# test-jauge.net
KiCad netlist of a schematic drawn in EAGLE
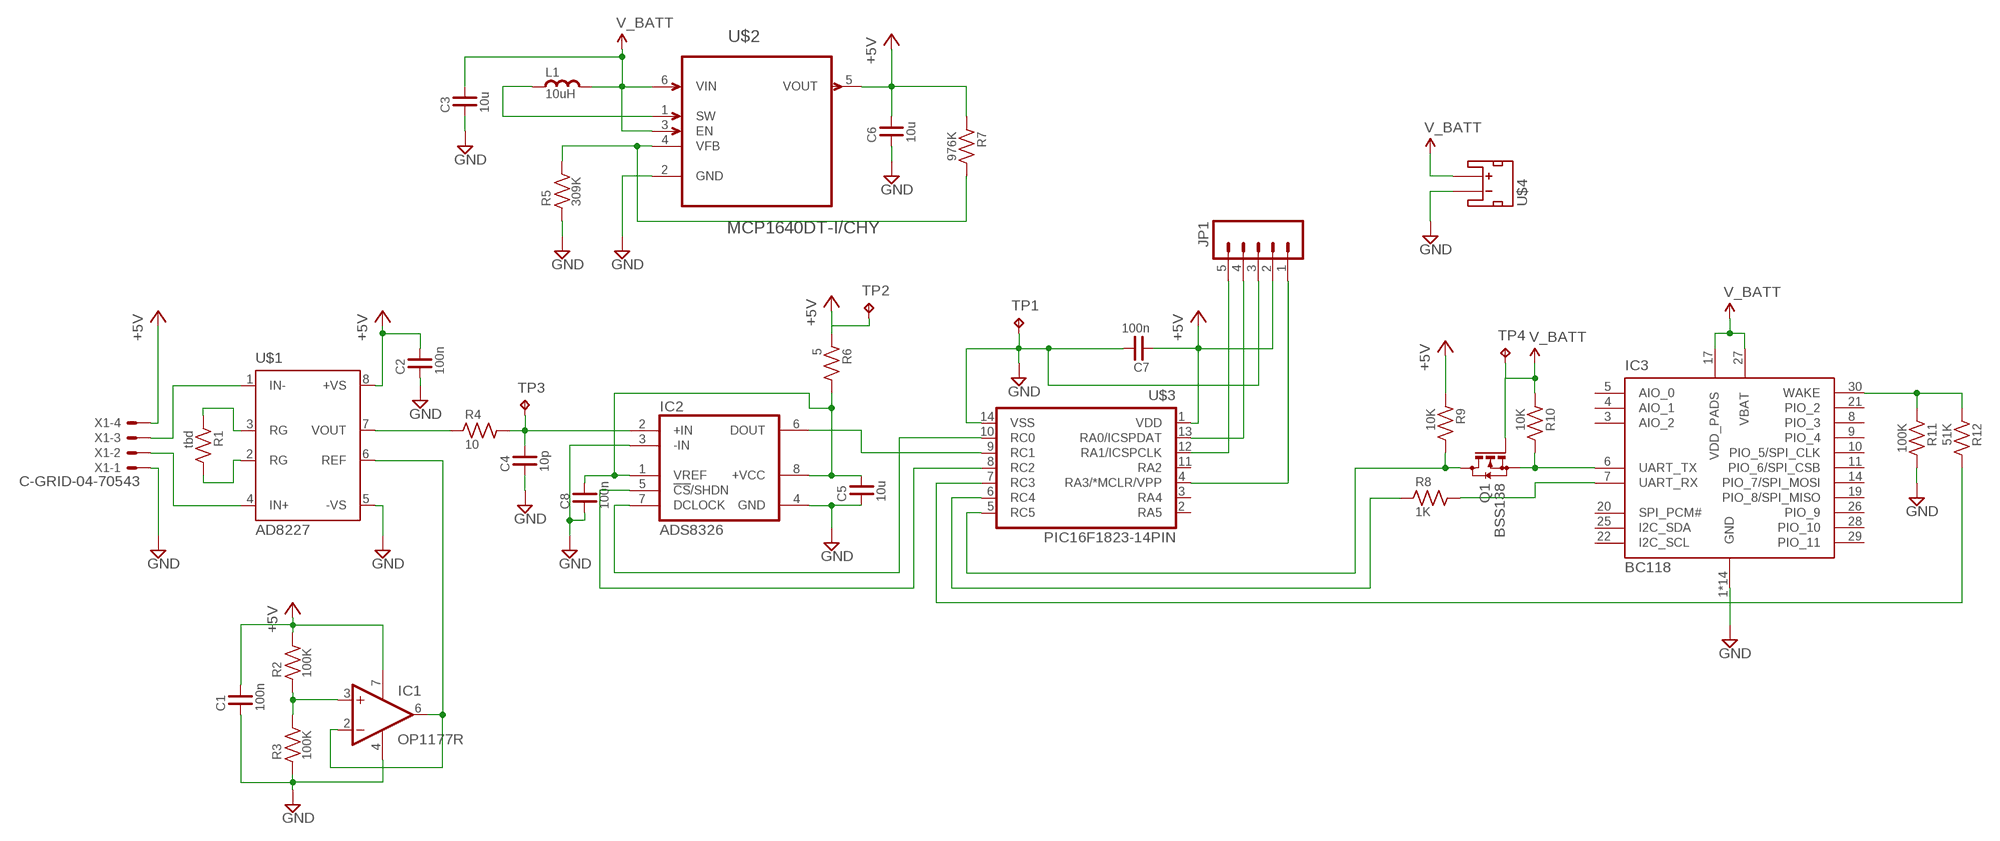
[diagram p0: schematic, sheet 1]

(export (version "E")
  (design (tool "Eeschema 10.0.6"))
  (components
    (comp (ref "C1")
      (value "100n")
      (footprint "eagle-import:C1206")
      (libsource (lib "eagle-import") (part "C1206"))
    )
    (comp (ref "C2")
      (value "100n")
      (footprint "eagle-import:C1206")
      (libsource (lib "eagle-import") (part "C1206"))
    )
    (comp (ref "C3")
      (value "10u")
      (footprint "eagle-import:C1206")
      (libsource (lib "eagle-import") (part "C1206"))
    )
    (comp (ref "C4")
      (value "10p")
      (footprint "eagle-import:C1206")
      (libsource (lib "eagle-import") (part "C1206"))
    )
    (comp (ref "C5")
      (value "10u")
      (footprint "eagle-import:C1206")
      (libsource (lib "eagle-import") (part "C1206"))
    )
    (comp (ref "C6")
      (value "10u")
      (footprint "eagle-import:C1206")
      (libsource (lib "eagle-import") (part "C1206"))
    )
    (comp (ref "C7")
      (value "100n")
      (footprint "eagle-import:C1206")
      (libsource (lib "eagle-import") (part "C1206"))
    )
    (comp (ref "C8")
      (value "100n")
      (footprint "eagle-import:C1206")
      (libsource (lib "eagle-import") (part "C1206"))
    )
    (comp (ref "IC1")
      (value "OP1177R")
      (footprint "eagle-import:SOIC8")
      (libsource (lib "eagle-import") (part "OP1177R"))
    )
    (comp (ref "IC2")
      (value "ADS8326")
      (footprint "eagle-import:MSOP08")
      (fields (field (name "MF") "TEXAS INSTRUMENT CONNECTORS") (field (name "MPN") "ADS7816EC/250"))
      (libsource (lib "eagle-import") (part "ADS7816E"))
    )
    (comp (ref "IC3")
      (value "BC118")
      (footprint "eagle-import:BC118")
      (libsource (lib "eagle-import") (part "BC118"))
    )
    (comp (ref "JP1")
      (value "M05PTH")
      (footprint "eagle-import:1X05")
      (libsource (lib "eagle-import") (part "M05PTH"))
    )
    (comp (ref "L1")
      (value "10uH")
      (footprint "eagle-import:L1206")
      (libsource (lib "eagle-import") (part "LU1206"))
    )
    (comp (ref "Q1")
      (value "BSS138")
      (footprint "eagle-import:SOT23")
      (libsource (lib "eagle-import") (part "BSS123"))
    )
    (comp (ref "R1")
      (value "tbd")
      (footprint "eagle-import:R1206")
      (libsource (lib "eagle-import") (part "RU1206"))
    )
    (comp (ref "R2")
      (value "100K")
      (footprint "eagle-import:R1206")
      (libsource (lib "eagle-import") (part "RU1206"))
    )
    (comp (ref "R3")
      (value "100K")
      (footprint "eagle-import:R1206")
      (libsource (lib "eagle-import") (part "RU1206"))
    )
    (comp (ref "R4")
      (value "10")
      (footprint "eagle-import:R1206")
      (libsource (lib "eagle-import") (part "RU1206"))
    )
    (comp (ref "R5")
      (value "309K")
      (footprint "eagle-import:R1206")
      (libsource (lib "eagle-import") (part "RU1206"))
    )
    (comp (ref "R6")
      (value "5")
      (footprint "eagle-import:R1206")
      (libsource (lib "eagle-import") (part "RU1206"))
    )
    (comp (ref "R7")
      (value "976K")
      (footprint "eagle-import:R1206")
      (libsource (lib "eagle-import") (part "RU1206"))
    )
    (comp (ref "R8")
      (value "1K")
      (footprint "eagle-import:R1206")
      (libsource (lib "eagle-import") (part "RU1206"))
    )
    (comp (ref "R9")
      (value "10K")
      (footprint "eagle-import:R1206")
      (libsource (lib "eagle-import") (part "RU1206"))
    )
    (comp (ref "R10")
      (value "10K")
      (footprint "eagle-import:R1206")
      (libsource (lib "eagle-import") (part "RU1206"))
    )
    (comp (ref "R11")
      (value "100K")
      (footprint "eagle-import:R1206")
      (libsource (lib "eagle-import") (part "RU1206"))
    )
    (comp (ref "R12")
      (value "51K")
      (footprint "eagle-import:R1206")
      (libsource (lib "eagle-import") (part "RU1206"))
    )
    (comp (ref "TP1")
      (value "TPTP08R")
      (footprint "eagle-import:TP08R")
      (libsource (lib "eagle-import") (part "TPTP08R"))
    )
    (comp (ref "TP2")
      (value "TPTP08R")
      (footprint "eagle-import:TP08R")
      (libsource (lib "eagle-import") (part "TPTP08R"))
    )
    (comp (ref "TP3")
      (value "TPTP08R")
      (footprint "eagle-import:TP08R")
      (libsource (lib "eagle-import") (part "TPTP08R"))
    )
    (comp (ref "TP4")
      (value "TPTP08R")
      (footprint "eagle-import:TP08R")
      (libsource (lib "eagle-import") (part "TPTP08R"))
    )
    (comp (ref "U$1")
      (value "AD8227")
      (footprint "eagle-import:SO8")
      (libsource (lib "eagle-import") (part "AD822X"))
    )
    (comp (ref "U$2")
      (value "MCP1640DT-I/CHY")
      (footprint "eagle-import:SOT95P270X145-6N")
      (libsource (lib "eagle-import") (part "MCP1640DT-I/CHY"))
    )
    (comp (ref "U$3")
      (value "PIC16F1823-14PIN")
      (footprint "eagle-import:SOIC-14")
      (libsource (lib "eagle-import") (part "PIC16F1823-14PIN"))
    )
    (comp (ref "U$4")
      (value "JST-2-PTH")
      (footprint "eagle-import:JST-2-PTH")
      (libsource (lib "eagle-import") (part "JST-2-PTH"))
    )
    (comp (ref "X1")
      (value "C-GRID-04-70543")
      (footprint "eagle-import:70543-04")
      (libsource (lib "eagle-import") (part "C-GRID-04-70543"))
    )
  )
  (nets
    (net (code "1") (name "+5V") (class "Default")
      (node (ref "C1") (pin "2") (pinfunction "2_2") (pintype "passive"))
      (node (ref "C2") (pin "2") (pinfunction "2_2") (pintype "passive"))
      (node (ref "C6") (pin "2") (pinfunction "2_2") (pintype "passive"))
      (node (ref "C7") (pin "1") (pinfunction "1_1") (pintype "passive"))
      (node (ref "IC1") (pin "7") (pinfunction "V+_7") (pintype "power_in"))
      (node (ref "JP1") (pin "2") (pinfunction "2_2") (pintype "passive"))
      (node (ref "R2") (pin "2") (pinfunction "2_2") (pintype "passive"))
      (node (ref "R6") (pin "1") (pinfunction "1_1") (pintype "passive"))
      (node (ref "R7") (pin "1") (pinfunction "1_1") (pintype "passive"))
      (node (ref "R9") (pin "1") (pinfunction "1_1") (pintype "passive"))
      (node (ref "TP2") (pin "TP") (pinfunction "TP_TP") (pintype "input"))
      (node (ref "U$1") (pin "8") (pinfunction "+VS_8") (pintype "power_in"))
      (node (ref "U$2") (pin "5") (pinfunction "VOUT_5") (pintype "output"))
      (node (ref "U$3") (pin "1") (pinfunction "VDD_1") (pintype "power_in"))
      (node (ref "X1") (pin "4") (pinfunction "S_4") (pintype "passive"))
    )
    (net (code "2") (name "GND") (class "Default")
      (node (ref "C1") (pin "1") (pinfunction "1_1") (pintype "passive"))
      (node (ref "C2") (pin "1") (pinfunction "1_1") (pintype "passive"))
      (node (ref "C3") (pin "1") (pinfunction "1_1") (pintype "passive"))
      (node (ref "C4") (pin "1") (pinfunction "1_1") (pintype "passive"))
      (node (ref "C5") (pin "1") (pinfunction "1_1") (pintype "passive"))
      (node (ref "C6") (pin "1") (pinfunction "1_1") (pintype "passive"))
      (node (ref "C7") (pin "2") (pinfunction "2_2") (pintype "passive"))
      (node (ref "C8") (pin "1") (pinfunction "1_1") (pintype "passive"))
      (node (ref "IC1") (pin "4") (pinfunction "V-_4") (pintype "power_in"))
      (node (ref "IC2") (pin "3") (pinfunction "-IN_3") (pintype "input"))
      (node (ref "IC2") (pin "4") (pinfunction "GND_4") (pintype "power_in"))
      (node (ref "IC3") (pin "1") (pinfunction "GND_1") (pintype "power_in"))
      (node (ref "IC3") (pin "12") (pinfunction "GND_12") (pintype "power_in"))
      (node (ref "IC3") (pin "13") (pinfunction "GND_13") (pintype "power_in"))
      (node (ref "IC3") (pin "15") (pinfunction "GND_15") (pintype "power_in"))
      (node (ref "IC3") (pin "16") (pinfunction "GND_16") (pintype "power_in"))
      (node (ref "IC3") (pin "18") (pinfunction "GND_18") (pintype "power_in"))
      (node (ref "IC3") (pin "2") (pinfunction "GND_2") (pintype "power_in"))
      (node (ref "IC3") (pin "23") (pinfunction "GND_23") (pintype "power_in"))
      (node (ref "IC3") (pin "24") (pinfunction "GND_24") (pintype "power_in"))
      (node (ref "IC3") (pin "31") (pinfunction "GND_31") (pintype "power_in"))
      (node (ref "IC3") (pin "32") (pinfunction "GND_32") (pintype "power_in"))
      (node (ref "IC3") (pin "33") (pinfunction "GND_33") (pintype "power_in"))
      (node (ref "IC3") (pin "34") (pinfunction "GND_34") (pintype "power_in"))
      (node (ref "IC3") (pin "35") (pinfunction "GND_35") (pintype "power_in"))
      (node (ref "JP1") (pin "3") (pinfunction "3_3") (pintype "passive"))
      (node (ref "R11") (pin "2") (pinfunction "2_2") (pintype "passive"))
      (node (ref "R3") (pin "1") (pinfunction "1_1") (pintype "passive"))
      (node (ref "R5") (pin "1") (pinfunction "1_1") (pintype "passive"))
      (node (ref "TP1") (pin "TP") (pinfunction "TP_TP") (pintype "input"))
      (node (ref "U$1") (pin "5") (pinfunction "-VS_5") (pintype "power_in"))
      (node (ref "U$2") (pin "2") (pinfunction "GND_2") (pintype "passive"))
      (node (ref "U$3") (pin "14") (pinfunction "VSS_14") (pintype "power_in"))
      (node (ref "U$4") (pin "-") (pinfunction "-_-") (pintype "bidirectional"))
      (node (ref "X1") (pin "1") (pinfunction "S_1") (pintype "passive"))
    )
    (net (code "3") (name "Net-(IC1-+IN)") (class "Default")
      (node (ref "IC1") (pin "3") (pinfunction "+IN_3") (pintype "input"))
      (node (ref "R2") (pin "1") (pinfunction "1_1") (pintype "passive"))
      (node (ref "R3") (pin "2") (pinfunction "2_2") (pintype "passive"))
    )
    (net (code "4") (name "Net-(IC1--IN)") (class "Default")
      (node (ref "IC1") (pin "2") (pinfunction "-IN_2") (pintype "input"))
      (node (ref "IC1") (pin "6") (pinfunction "OUT_6") (pintype "output"))
      (node (ref "U$1") (pin "6") (pinfunction "REF_6") (pintype "input"))
    )
    (net (code "5") (name "Net-(IC2-+IN)") (class "Default")
      (node (ref "C4") (pin "2") (pinfunction "2_2") (pintype "passive"))
      (node (ref "IC2") (pin "2") (pinfunction "+IN_2") (pintype "input"))
      (node (ref "R4") (pin "2") (pinfunction "2_2") (pintype "passive"))
      (node (ref "TP3") (pin "TP") (pinfunction "TP_TP") (pintype "input"))
    )
    (net (code "6") (name "Net-(IC2-+VCC)") (class "Default")
      (node (ref "C5") (pin "2") (pinfunction "2_2") (pintype "passive"))
      (node (ref "C8") (pin "2") (pinfunction "2_2") (pintype "passive"))
      (node (ref "IC2") (pin "1") (pinfunction "VREF_1") (pintype "input"))
      (node (ref "IC2") (pin "8") (pinfunction "+VCC_8") (pintype "power_in"))
      (node (ref "R6") (pin "2") (pinfunction "2_2") (pintype "passive"))
    )
    (net (code "7") (name "Net-(IC2-DCLOCK)") (class "Default")
      (node (ref "IC2") (pin "7") (pinfunction "DCLOCK_7") (pintype "input"))
      (node (ref "U$3") (pin "10") (pinfunction "RC0_10") (pintype "bidirectional"))
    )
    (net (code "8") (name "Net-(IC2-DOUT)") (class "Default")
      (node (ref "IC2") (pin "6") (pinfunction "DOUT_6") (pintype "output"))
      (node (ref "U$3") (pin "9") (pinfunction "RC1_9") (pintype "bidirectional"))
    )
    (net (code "9") (name "Net-(IC2-~{CS}{slash}SHDN)") (class "Default")
      (node (ref "IC2") (pin "5") (pinfunction "~{CS}/SHDN_5") (pintype "input"))
      (node (ref "U$3") (pin "8") (pinfunction "RC2_8") (pintype "bidirectional"))
    )
    (net (code "10") (name "Net-(IC3-UART_RX)") (class "Default")
      (node (ref "IC3") (pin "7") (pinfunction "UART_RX_7") (pintype "bidirectional"))
      (node (ref "R8") (pin "2") (pinfunction "2_2") (pintype "passive"))
    )
    (net (code "11") (name "Net-(IC3-UART_TX)") (class "Default")
      (node (ref "IC3") (pin "6") (pinfunction "UART_TX_6") (pintype "bidirectional"))
      (node (ref "Q1") (pin "2") (pinfunction "S_2") (pintype "passive"))
      (node (ref "R10") (pin "2") (pinfunction "2_2") (pintype "passive"))
    )
    (net (code "12") (name "Net-(IC3-WAKE)") (class "Default")
      (node (ref "IC3") (pin "30") (pinfunction "WAKE_30") (pintype "bidirectional"))
      (node (ref "R11") (pin "1") (pinfunction "1_1") (pintype "passive"))
      (node (ref "R12") (pin "1") (pinfunction "1_1") (pintype "passive"))
    )
    (net (code "13") (name "Net-(Q1-D)") (class "Default")
      (node (ref "Q1") (pin "3") (pinfunction "D_3") (pintype "passive"))
      (node (ref "R9") (pin "2") (pinfunction "2_2") (pintype "passive"))
      (node (ref "U$3") (pin "5") (pinfunction "RC5_5") (pintype "bidirectional"))
    )
    (net (code "14") (name "Net-(R1-Pad1)") (class "Default")
      (node (ref "R1") (pin "1") (pinfunction "1_1") (pintype "passive"))
      (node (ref "U$1") (pin "3") (pinfunction "RG_3") (pintype "input"))
    )
    (net (code "15") (name "Net-(R1-Pad2)") (class "Default")
      (node (ref "R1") (pin "2") (pinfunction "2_2") (pintype "passive"))
      (node (ref "U$1") (pin "2") (pinfunction "RG_2") (pintype "input"))
    )
    (net (code "16") (name "Net-(U$1-IN+)") (class "Default")
      (node (ref "U$1") (pin "4") (pinfunction "IN+_4") (pintype "input"))
      (node (ref "X1") (pin "2") (pinfunction "S_2") (pintype "passive"))
    )
    (net (code "17") (name "Net-(U$1-IN-)") (class "Default")
      (node (ref "U$1") (pin "1") (pinfunction "IN-_1") (pintype "input"))
      (node (ref "X1") (pin "3") (pinfunction "S_3") (pintype "passive"))
    )
    (net (code "18") (name "Net-(U$1-VOUT)") (class "Default")
      (node (ref "R4") (pin "1") (pinfunction "1_1") (pintype "passive"))
      (node (ref "U$1") (pin "7") (pinfunction "VOUT_7") (pintype "output"))
    )
    (net (code "19") (name "Net-(U$2-SW)") (class "Default")
      (node (ref "L1") (pin "1") (pinfunction "1_1") (pintype "passive"))
      (node (ref "U$2") (pin "1") (pinfunction "SW_1") (pintype "input"))
    )
    (net (code "20") (name "Net-(U$2-VFB)") (class "Default")
      (node (ref "R5") (pin "2") (pinfunction "2_2") (pintype "passive"))
      (node (ref "R7") (pin "2") (pinfunction "2_2") (pintype "passive"))
      (node (ref "U$2") (pin "4") (pinfunction "VFB_4") (pintype "input"))
    )
    (net (code "21") (name "Net-(U$3-RA0{slash}ICSPDAT)") (class "Default")
      (node (ref "JP1") (pin "4") (pinfunction "4_4") (pintype "passive"))
      (node (ref "U$3") (pin "13") (pinfunction "RA0/ICSPDAT_13") (pintype "bidirectional"))
    )
    (net (code "22") (name "Net-(U$3-RA1{slash}ICSPCLK)") (class "Default")
      (node (ref "JP1") (pin "5") (pinfunction "5_5") (pintype "passive"))
      (node (ref "U$3") (pin "12") (pinfunction "RA1/ICSPCLK_12") (pintype "bidirectional"))
    )
    (net (code "23") (name "Net-(U$3-RA3{slash}*MCLR{slash}VPP)") (class "Default")
      (node (ref "JP1") (pin "1") (pinfunction "1_1") (pintype "passive"))
      (node (ref "U$3") (pin "4") (pinfunction "RA3/*MCLR/VPP_4") (pintype "input"))
    )
    (net (code "24") (name "Net-(U$3-RC3)") (class "Default")
      (node (ref "R12") (pin "2") (pinfunction "2_2") (pintype "passive"))
      (node (ref "U$3") (pin "7") (pinfunction "RC3_7") (pintype "bidirectional"))
    )
    (net (code "25") (name "Net-(U$3-RC4)") (class "Default")
      (node (ref "R8") (pin "1") (pinfunction "1_1") (pintype "passive"))
      (node (ref "U$3") (pin "6") (pinfunction "RC4_6") (pintype "bidirectional"))
    )
    (net (code "26") (name "V_BATT") (class "Default")
      (node (ref "C3") (pin "2") (pinfunction "2_2") (pintype "passive"))
      (node (ref "IC3") (pin "17") (pinfunction "VDD_PADS_17") (pintype "power_in"))
      (node (ref "IC3") (pin "27") (pinfunction "VBAT_27") (pintype "bidirectional"))
      (node (ref "L1") (pin "2") (pinfunction "2_2") (pintype "passive"))
      (node (ref "Q1") (pin "1") (pinfunction "G_1") (pintype "passive"))
      (node (ref "R10") (pin "1") (pinfunction "1_1") (pintype "passive"))
      (node (ref "TP4") (pin "TP") (pinfunction "TP_TP") (pintype "input"))
      (node (ref "U$2") (pin "3") (pinfunction "EN_3") (pintype "input"))
      (node (ref "U$2") (pin "6") (pinfunction "VIN_6") (pintype "input"))
      (node (ref "U$4") (pin "+") (pinfunction "+_+") (pintype "bidirectional"))
    )
    (net (code "27") (name "unconnected-(IC3-AIO_0-Pad5)") (class "Default")
      (node (ref "IC3") (pin "5") (pinfunction "AIO_0_5") (pintype "bidirectional"))
    )
    (net (code "28") (name "unconnected-(IC3-AIO_1-Pad4)") (class "Default")
      (node (ref "IC3") (pin "4") (pinfunction "AIO_1_4") (pintype "bidirectional"))
    )
    (net (code "29") (name "unconnected-(IC3-AIO_2-Pad3)") (class "Default")
      (node (ref "IC3") (pin "3") (pinfunction "AIO_2_3") (pintype "bidirectional"))
    )
    (net (code "30") (name "unconnected-(IC3-I2C_SCL-Pad22)") (class "Default")
      (node (ref "IC3") (pin "22") (pinfunction "I2C_SCL_22") (pintype "bidirectional"))
    )
    (net (code "31") (name "unconnected-(IC3-I2C_SDA-Pad25)") (class "Default")
      (node (ref "IC3") (pin "25") (pinfunction "I2C_SDA_25") (pintype "bidirectional"))
    )
    (net (code "32") (name "unconnected-(IC3-PIO_2-Pad21)") (class "Default")
      (node (ref "IC3") (pin "21") (pinfunction "PIO_2_21") (pintype "bidirectional"))
    )
    (net (code "33") (name "unconnected-(IC3-PIO_3-Pad8)") (class "Default")
      (node (ref "IC3") (pin "8") (pinfunction "PIO_3_8") (pintype "bidirectional"))
    )
    (net (code "34") (name "unconnected-(IC3-PIO_4-Pad9)") (class "Default")
      (node (ref "IC3") (pin "9") (pinfunction "PIO_4_9") (pintype "bidirectional"))
    )
    (net (code "35") (name "unconnected-(IC3-PIO_5{slash}SPI_CLK-Pad10)") (class "Default")
      (node (ref "IC3") (pin "10") (pinfunction "PIO_5/SPI_CLK_10") (pintype "bidirectional"))
    )
    (net (code "36") (name "unconnected-(IC3-PIO_6{slash}SPI_CSB-Pad11)") (class "Default")
      (node (ref "IC3") (pin "11") (pinfunction "PIO_6/SPI_CSB_11") (pintype "bidirectional"))
    )
    (net (code "37") (name "unconnected-(IC3-PIO_7{slash}SPI_MOSI-Pad14)") (class "Default")
      (node (ref "IC3") (pin "14") (pinfunction "PIO_7/SPI_MOSI_14") (pintype "bidirectional"))
    )
    (net (code "38") (name "unconnected-(IC3-PIO_8{slash}SPI_MISO-Pad19)") (class "Default")
      (node (ref "IC3") (pin "19") (pinfunction "PIO_8/SPI_MISO_19") (pintype "bidirectional"))
    )
    (net (code "39") (name "unconnected-(IC3-PIO_9-Pad26)") (class "Default")
      (node (ref "IC3") (pin "26") (pinfunction "PIO_9_26") (pintype "bidirectional"))
    )
    (net (code "40") (name "unconnected-(IC3-PIO_10-Pad28)") (class "Default")
      (node (ref "IC3") (pin "28") (pinfunction "PIO_10_28") (pintype "bidirectional"))
    )
    (net (code "41") (name "unconnected-(IC3-PIO_11-Pad29)") (class "Default")
      (node (ref "IC3") (pin "29") (pinfunction "PIO_11_29") (pintype "bidirectional"))
    )
    (net (code "42") (name "unconnected-(IC3-SPI_PCM#-Pad20)") (class "Default")
      (node (ref "IC3") (pin "20") (pinfunction "SPI_PCM#_20") (pintype "input"))
    )
    (net (code "43") (name "unconnected-(U$3-RA2-Pad11)") (class "Default")
      (node (ref "U$3") (pin "11") (pinfunction "RA2_11") (pintype "bidirectional"))
    )
    (net (code "44") (name "unconnected-(U$3-RA4-Pad3)") (class "Default")
      (node (ref "U$3") (pin "3") (pinfunction "RA4_3") (pintype "bidirectional"))
    )
    (net (code "45") (name "unconnected-(U$3-RA5-Pad2)") (class "Default")
      (node (ref "U$3") (pin "2") (pinfunction "RA5_2") (pintype "bidirectional"))
    )
  )
)
